# POGO_CPU.net
KiCad netlist of a schematic drawn in EAGLE
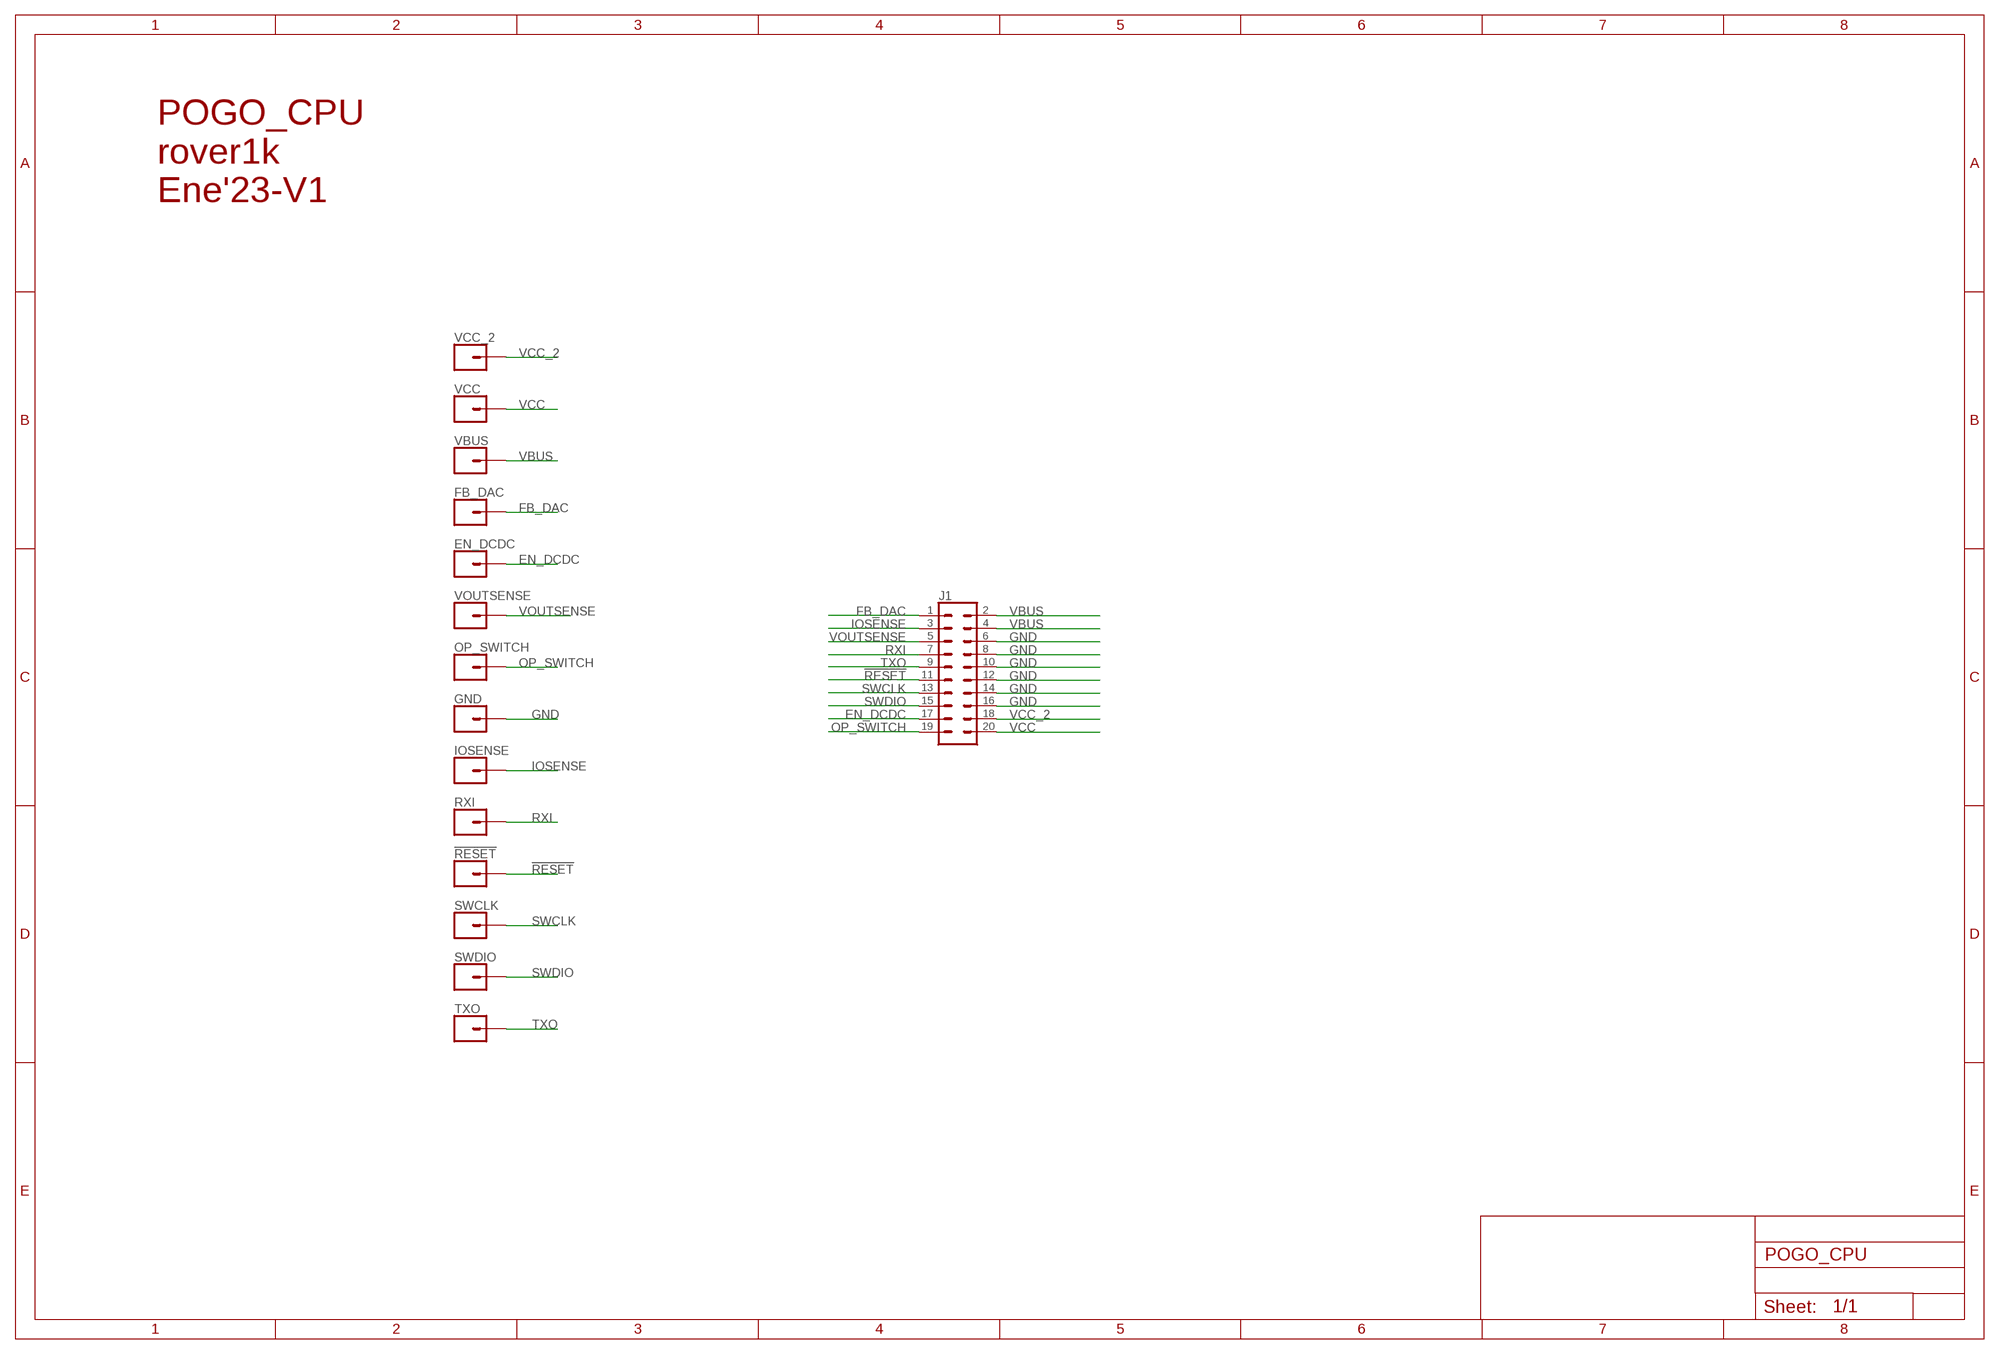
[diagram p0: schematic, sheet 1]

(export (version "E")
  (design (tool "Eeschema 10.0.6"))
  (components
    (comp (ref "!RESET")
      (value "CONN_01POGOPIN_HOLE_LARGE")
      (footprint "eagle-import:1X01_POGOPIN_HOLE_0.061_DIA")
      (libsource (lib "eagle-import") (part "CONN_01POGOPIN_HOLE_LARGE"))
    )
    (comp (ref "EN_DCDC")
      (value "CONN_01POGOPIN_HOLE_LARGE")
      (footprint "eagle-import:1X01_POGOPIN_HOLE_0.061_DIA")
      (libsource (lib "eagle-import") (part "CONN_01POGOPIN_HOLE_LARGE"))
    )
    (comp (ref "FB_DAC")
      (value "CONN_01POGOPIN_HOLE_LARGE")
      (footprint "eagle-import:1X01_POGOPIN_HOLE_0.061_DIA")
      (libsource (lib "eagle-import") (part "CONN_01POGOPIN_HOLE_LARGE"))
    )
    (comp (ref "GND")
      (value "CONN_01POGOPIN_HOLE_LARGE")
      (footprint "eagle-import:1X01_POGOPIN_HOLE_0.061_DIA")
      (libsource (lib "eagle-import") (part "CONN_01POGOPIN_HOLE_LARGE"))
    )
    (comp (ref "IOSENSE")
      (value "CONN_01POGOPIN_HOLE_LARGE")
      (footprint "eagle-import:1X01_POGOPIN_HOLE_0.061_DIA")
      (libsource (lib "eagle-import") (part "CONN_01POGOPIN_HOLE_LARGE"))
    )
    (comp (ref "J1")
      (value "CONN_10X2")
      (footprint "eagle-import:2X10")
      (libsource (lib "eagle-import") (part "CONN_10X2"))
    )
    (comp (ref "OP_SWITCH")
      (value "CONN_01POGOPIN_HOLE_LARGE")
      (footprint "eagle-import:1X01_POGOPIN_HOLE_0.061_DIA")
      (libsource (lib "eagle-import") (part "CONN_01POGOPIN_HOLE_LARGE"))
    )
    (comp (ref "RXI")
      (value "CONN_01POGOPIN_HOLE_LARGE")
      (footprint "eagle-import:1X01_POGOPIN_HOLE_0.061_DIA")
      (libsource (lib "eagle-import") (part "CONN_01POGOPIN_HOLE_LARGE"))
    )
    (comp (ref "SWCLK")
      (value "CONN_01POGOPIN_HOLE_LARGE")
      (footprint "eagle-import:1X01_POGOPIN_HOLE_0.061_DIA")
      (libsource (lib "eagle-import") (part "CONN_01POGOPIN_HOLE_LARGE"))
    )
    (comp (ref "SWDIO")
      (value "CONN_01POGOPIN_HOLE_LARGE")
      (footprint "eagle-import:1X01_POGOPIN_HOLE_0.061_DIA")
      (libsource (lib "eagle-import") (part "CONN_01POGOPIN_HOLE_LARGE"))
    )
    (comp (ref "TXO")
      (value "CONN_01POGOPIN_HOLE_LARGE")
      (footprint "eagle-import:1X01_POGOPIN_HOLE_0.061_DIA")
      (libsource (lib "eagle-import") (part "CONN_01POGOPIN_HOLE_LARGE"))
    )
    (comp (ref "VBUS")
      (value "CONN_01POGOPIN_HOLE_LARGE")
      (footprint "eagle-import:1X01_POGOPIN_HOLE_0.061_DIA")
      (libsource (lib "eagle-import") (part "CONN_01POGOPIN_HOLE_LARGE"))
    )
    (comp (ref "VCC")
      (value "CONN_01POGOPIN_HOLE_LARGE")
      (footprint "eagle-import:1X01_POGOPIN_HOLE_0.061_DIA")
      (libsource (lib "eagle-import") (part "CONN_01POGOPIN_HOLE_LARGE"))
    )
    (comp (ref "VCC_2")
      (value "CONN_01POGOPIN_HOLE_LARGE")
      (footprint "eagle-import:1X01_POGOPIN_HOLE_0.061_DIA")
      (libsource (lib "eagle-import") (part "CONN_01POGOPIN_HOLE_LARGE"))
    )
    (comp (ref "VOUTSENSE")
      (value "CONN_01POGOPIN_HOLE_LARGE")
      (footprint "eagle-import:1X01_POGOPIN_HOLE_0.061_DIA")
      (libsource (lib "eagle-import") (part "CONN_01POGOPIN_HOLE_LARGE"))
    )
  )
  (nets
    (net (code "1") (name "/EN_DCDC") (class "Default")
      (node (ref "EN_DCDC") (pin "2") (pinfunction "1_2") (pintype "passive"))
      (node (ref "J1") (pin "17") (pinfunction "17_17") (pintype "passive"))
    )
    (net (code "2") (name "/FB_DAC") (class "Default")
      (node (ref "FB_DAC") (pin "2") (pinfunction "1_2") (pintype "passive"))
      (node (ref "J1") (pin "1") (pinfunction "1_1") (pintype "passive"))
    )
    (net (code "3") (name "/GND") (class "Default")
      (node (ref "GND") (pin "2") (pinfunction "1_2") (pintype "passive"))
      (node (ref "J1") (pin "10") (pinfunction "10_10") (pintype "passive"))
      (node (ref "J1") (pin "12") (pinfunction "12_12") (pintype "passive"))
      (node (ref "J1") (pin "14") (pinfunction "14_14") (pintype "passive"))
      (node (ref "J1") (pin "16") (pinfunction "16_16") (pintype "passive"))
      (node (ref "J1") (pin "6") (pinfunction "6_6") (pintype "passive"))
      (node (ref "J1") (pin "8") (pinfunction "8_8") (pintype "passive"))
    )
    (net (code "4") (name "/IOSENSE") (class "Default")
      (node (ref "IOSENSE") (pin "2") (pinfunction "1_2") (pintype "passive"))
      (node (ref "J1") (pin "3") (pinfunction "3_3") (pintype "passive"))
    )
    (net (code "5") (name "/OP_SWITCH") (class "Default")
      (node (ref "J1") (pin "19") (pinfunction "19_19") (pintype "passive"))
      (node (ref "OP_SWITCH") (pin "2") (pinfunction "1_2") (pintype "passive"))
    )
    (net (code "6") (name "/RXI") (class "Default")
      (node (ref "J1") (pin "7") (pinfunction "7_7") (pintype "passive"))
      (node (ref "RXI") (pin "2") (pinfunction "1_2") (pintype "passive"))
    )
    (net (code "7") (name "/SWCLK") (class "Default")
      (node (ref "J1") (pin "13") (pinfunction "13_13") (pintype "passive"))
      (node (ref "SWCLK") (pin "2") (pinfunction "1_2") (pintype "passive"))
    )
    (net (code "8") (name "/SWDIO") (class "Default")
      (node (ref "J1") (pin "15") (pinfunction "15_15") (pintype "passive"))
      (node (ref "SWDIO") (pin "2") (pinfunction "1_2") (pintype "passive"))
    )
    (net (code "9") (name "/TXO") (class "Default")
      (node (ref "J1") (pin "9") (pinfunction "9_9") (pintype "passive"))
      (node (ref "TXO") (pin "2") (pinfunction "1_2") (pintype "passive"))
    )
    (net (code "10") (name "/VBUS") (class "Default")
      (node (ref "J1") (pin "2") (pinfunction "2_2") (pintype "passive"))
      (node (ref "J1") (pin "4") (pinfunction "4_4") (pintype "passive"))
      (node (ref "VBUS") (pin "2") (pinfunction "1_2") (pintype "passive"))
    )
    (net (code "11") (name "/VCC") (class "Default")
      (node (ref "J1") (pin "20") (pinfunction "20_20") (pintype "passive"))
      (node (ref "VCC") (pin "2") (pinfunction "1_2") (pintype "passive"))
    )
    (net (code "12") (name "/VCC_2") (class "Default")
      (node (ref "J1") (pin "18") (pinfunction "18_18") (pintype "passive"))
      (node (ref "VCC_2") (pin "2") (pinfunction "1_2") (pintype "passive"))
    )
    (net (code "13") (name "/VOUTSENSE") (class "Default")
      (node (ref "J1") (pin "5") (pinfunction "5_5") (pintype "passive"))
      (node (ref "VOUTSENSE") (pin "2") (pinfunction "1_2") (pintype "passive"))
    )
    (net (code "14") (name "/~{RESET}") (class "Default")
      (node (ref "!RESET") (pin "2") (pinfunction "1_2") (pintype "passive"))
      (node (ref "J1") (pin "11") (pinfunction "11_11") (pintype "passive"))
    )
  )
)
